# Auto_wiper.net
KiCad netlist of a schematic drawn in EAGLE
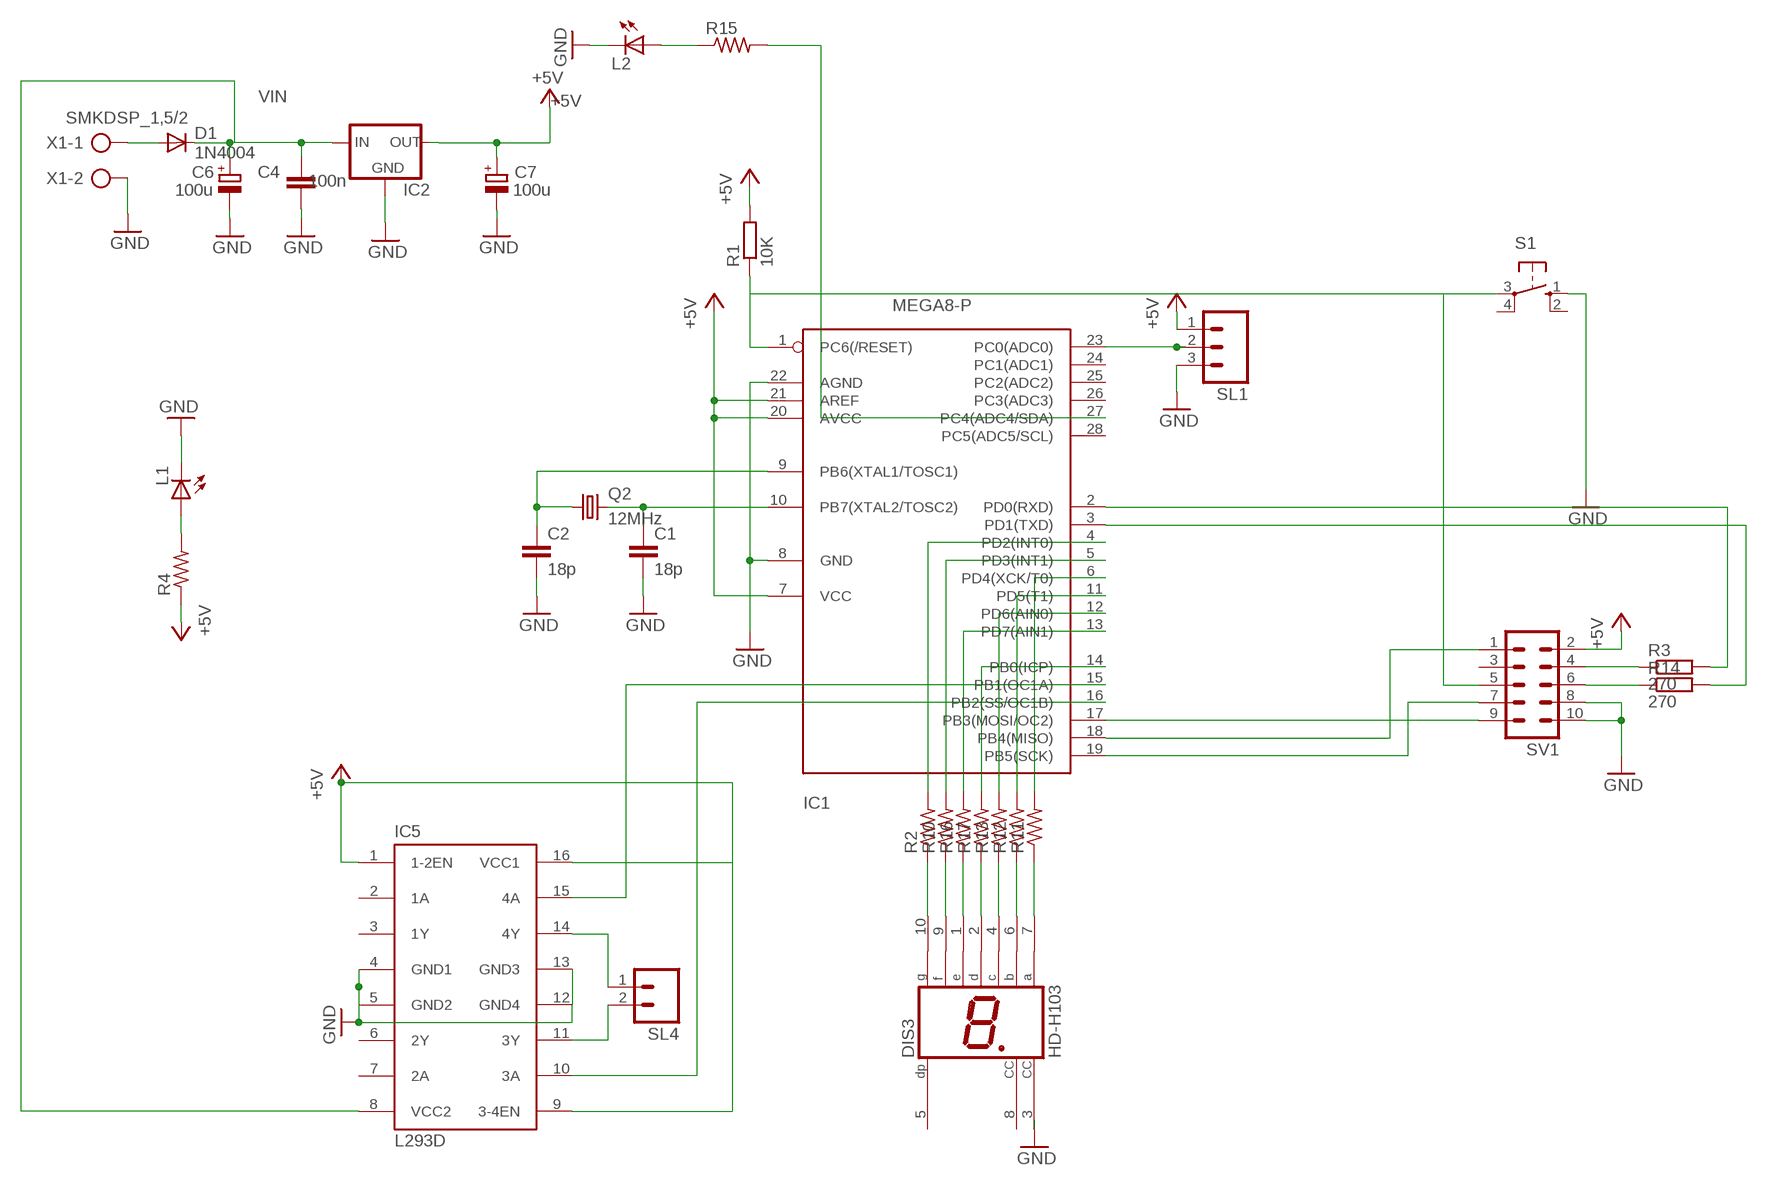
[diagram p0: schematic, sheet 1]

(export (version "E")
  (design (tool "Eeschema 10.0.6"))
  (components
    (comp (ref "C1")
      (value "18p")
      (footprint "eagle-import:C025-024X044")
      (libsource (lib "eagle-import") (part "C-EU025-024X044"))
    )
    (comp (ref "C2")
      (value "18p")
      (footprint "eagle-import:C025-024X044")
      (libsource (lib "eagle-import") (part "C-EU025-024X044"))
    )
    (comp (ref "C4")
      (value "100n")
      (footprint "eagle-import:C025-030X050")
      (libsource (lib "eagle-import") (part "resistor_C-EU025-030X050"))
    )
    (comp (ref "C6")
      (value "100u")
      (footprint "eagle-import:E3,5-8")
      (libsource (lib "eagle-import") (part "CPOL-EUE3.5-8"))
    )
    (comp (ref "C7")
      (value "100u")
      (footprint "eagle-import:E3,5-8")
      (libsource (lib "eagle-import") (part "CPOL-EUE3.5-8"))
    )
    (comp (ref "D1")
      (value "1N4004")
      (footprint "eagle-import:DO41-10")
      (libsource (lib "eagle-import") (part "1N4004"))
    )
    (comp (ref "DIS3")
      (value "HD-H103")
      (footprint "eagle-import:HDSP-M")
      (libsource (lib "eagle-import") (part "HD-H103"))
    )
    (comp (ref "IC1")
      (value "MEGA8-P")
      (footprint "eagle-import:DIL28-3")
      (libsource (lib "eagle-import") (part "MEGA8-P"))
    )
    (comp (ref "IC2")
      (value "78XXS")
      (footprint "eagle-import:78XXS")
      (libsource (lib "eagle-import") (part "78XXS"))
    )
    (comp (ref "IC5")
      (value "L293D")
      (footprint "eagle-import:DIL16")
      (libsource (lib "eagle-import") (part "L293D"))
    )
    (comp (ref "L1")
      (value "LED5MM")
      (footprint "eagle-import:LED5MM")
      (libsource (lib "eagle-import") (part "LED5MM"))
    )
    (comp (ref "L2")
      (value "LED5MM")
      (footprint "eagle-import:LED5MM")
      (libsource (lib "eagle-import") (part "LED5MM"))
    )
    (comp (ref "Q2")
      (value "12MHz")
      (footprint "eagle-import:HC49_S")
      (libsource (lib "eagle-import") (part "CRYTALHC49S"))
    )
    (comp (ref "R1")
      (value "10K")
      (footprint "eagle-import:0207_10")
      (libsource (lib "eagle-import") (part "R-EU_0207/10"))
    )
    (comp (ref "R2")
      (value "R-US_0207/10")
      (footprint "eagle-import:0207_10")
      (libsource (lib "eagle-import") (part "R-US_0207/10"))
    )
    (comp (ref "R3")
      (value "270")
      (footprint "eagle-import:0207_10")
      (libsource (lib "eagle-import") (part "R-EU_0207/10"))
    )
    (comp (ref "R4")
      (value "R-US_0207/10")
      (footprint "eagle-import:0207_10")
      (libsource (lib "eagle-import") (part "R-US_0207/10"))
    )
    (comp (ref "R10")
      (value "R-US_0207/10")
      (footprint "eagle-import:0207_10")
      (libsource (lib "eagle-import") (part "R-US_0207/10"))
    )
    (comp (ref "R11")
      (value "R-US_0207/10")
      (footprint "eagle-import:0207_10")
      (libsource (lib "eagle-import") (part "R-US_0207/10"))
    )
    (comp (ref "R12")
      (value "R-US_0207/10")
      (footprint "eagle-import:0207_10")
      (libsource (lib "eagle-import") (part "R-US_0207/10"))
    )
    (comp (ref "R13")
      (value "R-US_0207/10")
      (footprint "eagle-import:0207_10")
      (libsource (lib "eagle-import") (part "R-US_0207/10"))
    )
    (comp (ref "R14")
      (value "270")
      (footprint "eagle-import:0207_10")
      (libsource (lib "eagle-import") (part "R-EU_0207/10"))
    )
    (comp (ref "R15")
      (value "R-US_0207/10")
      (footprint "eagle-import:0207_10")
      (libsource (lib "eagle-import") (part "R-US_0207/10"))
    )
    (comp (ref "R16")
      (value "R-US_0207/10")
      (footprint "eagle-import:0207_10")
      (libsource (lib "eagle-import") (part "R-US_0207/10"))
    )
    (comp (ref "R17")
      (value "R-US_0207/10")
      (footprint "eagle-import:0207_10")
      (libsource (lib "eagle-import") (part "R-US_0207/10"))
    )
    (comp (ref "S1")
      (value "10-XX")
      (footprint "eagle-import:B3F-10XX")
      (fields (field (name "MPN") "B3F-1000"))
      (libsource (lib "eagle-import") (part "10-XX"))
    )
    (comp (ref "SL1")
      (value "M03")
      (footprint "eagle-import:03P")
      (libsource (lib "eagle-import") (part "M03"))
    )
    (comp (ref "SL4")
      (value "M02")
      (footprint "eagle-import:02P")
      (libsource (lib "eagle-import") (part "M02"))
    )
    (comp (ref "SV1")
      (value "ML10")
      (footprint "eagle-import:ML10")
      (libsource (lib "eagle-import") (part "ML10"))
    )
    (comp (ref "X1")
      (value "SMKDSP_1,5/2")
      (footprint "eagle-import:SMKDSP_1,5_2")
      (fields (field (name "MF") "FARNELL") (field (name "MPN") "1733570"))
      (libsource (lib "eagle-import") (part "SMKDSP_1,5/2"))
    )
  )
  (nets
    (net (code "1") (name "+5V") (class "Default")
      (node (ref "C7") (pin "+") (pinfunction "+_+") (pintype "passive"))
      (node (ref "IC1") (pin "20") (pinfunction "AVCC_20") (pintype "bidirectional"))
      (node (ref "IC1") (pin "21") (pinfunction "AREF_21") (pintype "bidirectional"))
      (node (ref "IC1") (pin "7") (pinfunction "VCC_7") (pintype "bidirectional"))
      (node (ref "IC2") (pin "OUT") (pinfunction "OUT_OUT") (pintype "passive"))
      (node (ref "IC5") (pin "1") (pinfunction "1-2EN_1") (pintype "input"))
      (node (ref "IC5") (pin "16") (pinfunction "VCC1_16") (pintype "power_in"))
      (node (ref "IC5") (pin "9") (pinfunction "3-4EN_9") (pintype "input"))
      (node (ref "R1") (pin "2") (pinfunction "2_2") (pintype "passive"))
      (node (ref "R4") (pin "1") (pinfunction "1_1") (pintype "passive"))
      (node (ref "SL1") (pin "1") (pinfunction "1_1") (pintype "passive"))
      (node (ref "SV1") (pin "2") (pinfunction "2_2") (pintype "passive"))
    )
    (net (code "2") (name "/VIN") (class "Default")
      (node (ref "C4") (pin "2") (pinfunction "2_2") (pintype "passive"))
      (node (ref "C6") (pin "+") (pinfunction "+_+") (pintype "passive"))
      (node (ref "D1") (pin "C") (pinfunction "C_C") (pintype "passive"))
      (node (ref "IC2") (pin "IN") (pinfunction "IN_IN") (pintype "input"))
      (node (ref "IC5") (pin "8") (pinfunction "VCC2_8") (pintype "power_in"))
    )
    (net (code "3") (name "GND") (class "Default")
      (node (ref "C1") (pin "2") (pinfunction "2_2") (pintype "passive"))
      (node (ref "C2") (pin "2") (pinfunction "2_2") (pintype "passive"))
      (node (ref "C4") (pin "1") (pinfunction "1_1") (pintype "passive"))
      (node (ref "C6") (pin "-") (pinfunction "-_-") (pintype "passive"))
      (node (ref "C7") (pin "-") (pinfunction "-_-") (pintype "passive"))
      (node (ref "DIS3") (pin "3") (pinfunction "CC_3") (pintype "passive"))
      (node (ref "IC1") (pin "22") (pinfunction "AGND_22") (pintype "bidirectional"))
      (node (ref "IC1") (pin "8") (pinfunction "GND_8") (pintype "bidirectional"))
      (node (ref "IC2") (pin "GND") (pinfunction "GND_GND") (pintype "input"))
      (node (ref "IC5") (pin "12") (pinfunction "GND4_12") (pintype "power_in"))
      (node (ref "IC5") (pin "13") (pinfunction "GND3_13") (pintype "power_in"))
      (node (ref "IC5") (pin "4") (pinfunction "GND1_4") (pintype "power_in"))
      (node (ref "IC5") (pin "5") (pinfunction "GND2_5") (pintype "power_in"))
      (node (ref "L1") (pin "K") (pinfunction "C_K") (pintype "passive"))
      (node (ref "L2") (pin "K") (pinfunction "C_K") (pintype "passive"))
      (node (ref "S1") (pin "1") (pinfunction "S_1") (pintype "passive"))
      (node (ref "SL1") (pin "3") (pinfunction "3_3") (pintype "passive"))
      (node (ref "SV1") (pin "10") (pinfunction "10_10") (pintype "passive"))
      (node (ref "SV1") (pin "8") (pinfunction "8_8") (pintype "passive"))
      (node (ref "X1") (pin "2") (pinfunction "KL_2") (pintype "passive"))
    )
    (net (code "4") (name "Net-(DIS3-A)") (class "Default")
      (node (ref "DIS3") (pin "7") (pinfunction "A_7") (pintype "passive"))
      (node (ref "R11") (pin "1") (pinfunction "1_1") (pintype "passive"))
    )
    (net (code "5") (name "Net-(DIS3-B)") (class "Default")
      (node (ref "DIS3") (pin "6") (pinfunction "B_6") (pintype "passive"))
      (node (ref "R12") (pin "1") (pinfunction "1_1") (pintype "passive"))
    )
    (net (code "6") (name "Net-(DIS3-C)") (class "Default")
      (node (ref "DIS3") (pin "4") (pinfunction "C_4") (pintype "passive"))
      (node (ref "R13") (pin "1") (pinfunction "1_1") (pintype "passive"))
    )
    (net (code "7") (name "Net-(DIS3-D)") (class "Default")
      (node (ref "DIS3") (pin "2") (pinfunction "D_2") (pintype "passive"))
      (node (ref "R17") (pin "1") (pinfunction "1_1") (pintype "passive"))
    )
    (net (code "8") (name "Net-(DIS3-E)") (class "Default")
      (node (ref "DIS3") (pin "1") (pinfunction "E_1") (pintype "passive"))
      (node (ref "R16") (pin "1") (pinfunction "1_1") (pintype "passive"))
    )
    (net (code "9") (name "Net-(DIS3-F)") (class "Default")
      (node (ref "DIS3") (pin "9") (pinfunction "F_9") (pintype "passive"))
      (node (ref "R10") (pin "1") (pinfunction "1_1") (pintype "passive"))
    )
    (net (code "10") (name "Net-(DIS3-G)") (class "Default")
      (node (ref "DIS3") (pin "10") (pinfunction "G_10") (pintype "passive"))
      (node (ref "R2") (pin "1") (pinfunction "1_1") (pintype "passive"))
    )
    (net (code "11") (name "Net-(IC1-PB0(ICP))") (class "Default")
      (node (ref "IC1") (pin "14") (pinfunction "PB0(ICP)_14") (pintype "bidirectional"))
      (node (ref "R17") (pin "2") (pinfunction "2_2") (pintype "passive"))
    )
    (net (code "12") (name "Net-(IC1-PB1(OC1A))") (class "Default")
      (node (ref "IC1") (pin "15") (pinfunction "PB1(OC1A)_15") (pintype "bidirectional"))
      (node (ref "IC5") (pin "15") (pinfunction "4A_15") (pintype "input"))
    )
    (net (code "13") (name "Net-(IC1-PB2(SS{slash}OC1B))") (class "Default")
      (node (ref "IC1") (pin "16") (pinfunction "PB2(SS/OC1B)_16") (pintype "bidirectional"))
      (node (ref "IC5") (pin "10") (pinfunction "3A_10") (pintype "input"))
    )
    (net (code "14") (name "Net-(IC1-PB3(MOSI{slash}OC2))") (class "Default")
      (node (ref "IC1") (pin "17") (pinfunction "PB3(MOSI/OC2)_17") (pintype "bidirectional"))
      (node (ref "SV1") (pin "9") (pinfunction "9_9") (pintype "passive"))
    )
    (net (code "15") (name "Net-(IC1-PB4(MISO))") (class "Default")
      (node (ref "IC1") (pin "18") (pinfunction "PB4(MISO)_18") (pintype "bidirectional"))
      (node (ref "SV1") (pin "1") (pinfunction "1_1") (pintype "passive"))
    )
    (net (code "16") (name "Net-(IC1-PB5(SCK))") (class "Default")
      (node (ref "IC1") (pin "19") (pinfunction "PB5(SCK)_19") (pintype "bidirectional"))
      (node (ref "SV1") (pin "7") (pinfunction "7_7") (pintype "passive"))
    )
    (net (code "17") (name "Net-(IC1-PB6(XTAL1{slash}TOSC1))") (class "Default")
      (node (ref "C2") (pin "1") (pinfunction "1_1") (pintype "passive"))
      (node (ref "IC1") (pin "9") (pinfunction "PB6(XTAL1/TOSC1)_9") (pintype "bidirectional"))
      (node (ref "Q2") (pin "1") (pinfunction "1_1") (pintype "passive"))
    )
    (net (code "18") (name "Net-(IC1-PB7(XTAL2{slash}TOSC2))") (class "Default")
      (node (ref "C1") (pin "1") (pinfunction "1_1") (pintype "passive"))
      (node (ref "IC1") (pin "10") (pinfunction "PB7(XTAL2/TOSC2)_10") (pintype "bidirectional"))
      (node (ref "Q2") (pin "2") (pinfunction "2_2") (pintype "passive"))
    )
    (net (code "19") (name "Net-(IC1-PC0(ADC0))") (class "Default")
      (node (ref "IC1") (pin "23") (pinfunction "PC0(ADC0)_23") (pintype "bidirectional"))
      (node (ref "SL1") (pin "2") (pinfunction "2_2") (pintype "passive"))
    )
    (net (code "20") (name "Net-(IC1-PC4(ADC4{slash}SDA))") (class "Default")
      (node (ref "IC1") (pin "27") (pinfunction "PC4(ADC4/SDA)_27") (pintype "bidirectional"))
      (node (ref "R15") (pin "2") (pinfunction "2_2") (pintype "passive"))
    )
    (net (code "21") (name "Net-(IC1-PC6({slash}RESET))") (class "Default")
      (node (ref "IC1") (pin "1") (pinfunction "PC6(/RESET)_1") (pintype "bidirectional"))
      (node (ref "R1") (pin "1") (pinfunction "1_1") (pintype "passive"))
      (node (ref "S1") (pin "3") (pinfunction "P_3") (pintype "passive"))
      (node (ref "SV1") (pin "5") (pinfunction "5_5") (pintype "passive"))
    )
    (net (code "22") (name "Net-(IC1-PD0(RXD))") (class "Default")
      (node (ref "IC1") (pin "2") (pinfunction "PD0(RXD)_2") (pintype "bidirectional"))
      (node (ref "R3") (pin "2") (pinfunction "2_2") (pintype "passive"))
    )
    (net (code "23") (name "Net-(IC1-PD1(TXD))") (class "Default")
      (node (ref "IC1") (pin "3") (pinfunction "PD1(TXD)_3") (pintype "bidirectional"))
      (node (ref "R14") (pin "2") (pinfunction "2_2") (pintype "passive"))
    )
    (net (code "24") (name "Net-(IC1-PD2(INT0))") (class "Default")
      (node (ref "IC1") (pin "4") (pinfunction "PD2(INT0)_4") (pintype "bidirectional"))
      (node (ref "R2") (pin "2") (pinfunction "2_2") (pintype "passive"))
    )
    (net (code "25") (name "Net-(IC1-PD3(INT1))") (class "Default")
      (node (ref "IC1") (pin "5") (pinfunction "PD3(INT1)_5") (pintype "bidirectional"))
      (node (ref "R10") (pin "2") (pinfunction "2_2") (pintype "passive"))
    )
    (net (code "26") (name "Net-(IC1-PD4(XCK{slash}T0))") (class "Default")
      (node (ref "IC1") (pin "6") (pinfunction "PD4(XCK/T0)_6") (pintype "bidirectional"))
      (node (ref "R11") (pin "2") (pinfunction "2_2") (pintype "passive"))
    )
    (net (code "27") (name "Net-(IC1-PD5(T1))") (class "Default")
      (node (ref "IC1") (pin "11") (pinfunction "PD5(T1)_11") (pintype "bidirectional"))
      (node (ref "R12") (pin "2") (pinfunction "2_2") (pintype "passive"))
    )
    (net (code "28") (name "Net-(IC1-PD6(AIN0))") (class "Default")
      (node (ref "IC1") (pin "12") (pinfunction "PD6(AIN0)_12") (pintype "bidirectional"))
      (node (ref "R13") (pin "2") (pinfunction "2_2") (pintype "passive"))
    )
    (net (code "29") (name "Net-(IC1-PD7(AIN1))") (class "Default")
      (node (ref "IC1") (pin "13") (pinfunction "PD7(AIN1)_13") (pintype "bidirectional"))
      (node (ref "R16") (pin "2") (pinfunction "2_2") (pintype "passive"))
    )
    (net (code "30") (name "Net-(IC5-3Y)") (class "Default")
      (node (ref "IC5") (pin "11") (pinfunction "3Y_11") (pintype "output"))
      (node (ref "SL4") (pin "2") (pinfunction "2_2") (pintype "passive"))
    )
    (net (code "31") (name "Net-(IC5-4Y)") (class "Default")
      (node (ref "IC5") (pin "14") (pinfunction "4Y_14") (pintype "output"))
      (node (ref "SL4") (pin "1") (pinfunction "1_1") (pintype "passive"))
    )
    (net (code "32") (name "Net-(L1-PadA)") (class "Default")
      (node (ref "L1") (pin "A") (pinfunction "A_A") (pintype "passive"))
      (node (ref "R4") (pin "2") (pinfunction "2_2") (pintype "passive"))
    )
    (net (code "33") (name "Net-(L2-PadA)") (class "Default")
      (node (ref "L2") (pin "A") (pinfunction "A_A") (pintype "passive"))
      (node (ref "R15") (pin "1") (pinfunction "1_1") (pintype "passive"))
    )
    (net (code "34") (name "Net-(R3-Pad1)") (class "Default")
      (node (ref "R3") (pin "1") (pinfunction "1_1") (pintype "passive"))
      (node (ref "SV1") (pin "4") (pinfunction "4_4") (pintype "passive"))
    )
    (net (code "35") (name "Net-(R14-Pad1)") (class "Default")
      (node (ref "R14") (pin "1") (pinfunction "1_1") (pintype "passive"))
      (node (ref "SV1") (pin "6") (pinfunction "6_6") (pintype "passive"))
    )
    (net (code "36") (name "Net-(X1A-KL)") (class "Default")
      (node (ref "D1") (pin "A") (pinfunction "A_A") (pintype "passive"))
      (node (ref "X1") (pin "1") (pinfunction "KL_1") (pintype "passive"))
    )
    (net (code "37") (name "unconnected-(DIS3-CC-Pad8)") (class "Default")
      (node (ref "DIS3") (pin "8") (pinfunction "CC_8") (pintype "passive"))
    )
    (net (code "38") (name "unconnected-(DIS3-DP-Pad5)") (class "Default")
      (node (ref "DIS3") (pin "5") (pinfunction "DP_5") (pintype "passive"))
    )
    (net (code "39") (name "unconnected-(IC1-PC1(ADC1)-Pad24)") (class "Default")
      (node (ref "IC1") (pin "24") (pinfunction "PC1(ADC1)_24") (pintype "bidirectional"))
    )
    (net (code "40") (name "unconnected-(IC1-PC2(ADC2)-Pad25)") (class "Default")
      (node (ref "IC1") (pin "25") (pinfunction "PC2(ADC2)_25") (pintype "bidirectional"))
    )
    (net (code "41") (name "unconnected-(IC1-PC3(ADC3)-Pad26)") (class "Default")
      (node (ref "IC1") (pin "26") (pinfunction "PC3(ADC3)_26") (pintype "bidirectional"))
    )
    (net (code "42") (name "unconnected-(IC1-PC5(ADC5{slash}SCL)-Pad28)") (class "Default")
      (node (ref "IC1") (pin "28") (pinfunction "PC5(ADC5/SCL)_28") (pintype "bidirectional"))
    )
    (net (code "43") (name "unconnected-(IC5-1A-Pad2)") (class "Default")
      (node (ref "IC5") (pin "2") (pinfunction "1A_2") (pintype "input"))
    )
    (net (code "44") (name "unconnected-(IC5-1Y-Pad3)") (class "Default")
      (node (ref "IC5") (pin "3") (pinfunction "1Y_3") (pintype "output"))
    )
    (net (code "45") (name "unconnected-(IC5-2A-Pad7)") (class "Default")
      (node (ref "IC5") (pin "7") (pinfunction "2A_7") (pintype "input"))
    )
    (net (code "46") (name "unconnected-(IC5-2Y-Pad6)") (class "Default")
      (node (ref "IC5") (pin "6") (pinfunction "2Y_6") (pintype "output"))
    )
    (net (code "47") (name "unconnected-(S1-P1-Pad4)") (class "Default")
      (node (ref "S1") (pin "4") (pinfunction "P1_4") (pintype "passive"))
    )
    (net (code "48") (name "unconnected-(S1-S1-Pad2)") (class "Default")
      (node (ref "S1") (pin "2") (pinfunction "S1_2") (pintype "passive"))
    )
    (net (code "49") (name "unconnected-(SV1-Pad3)") (class "Default")
      (node (ref "SV1") (pin "3") (pinfunction "3_3") (pintype "passive"))
    )
  )
)
